# indsensor.net
KiCad netlist of a schematic drawn in EAGLE
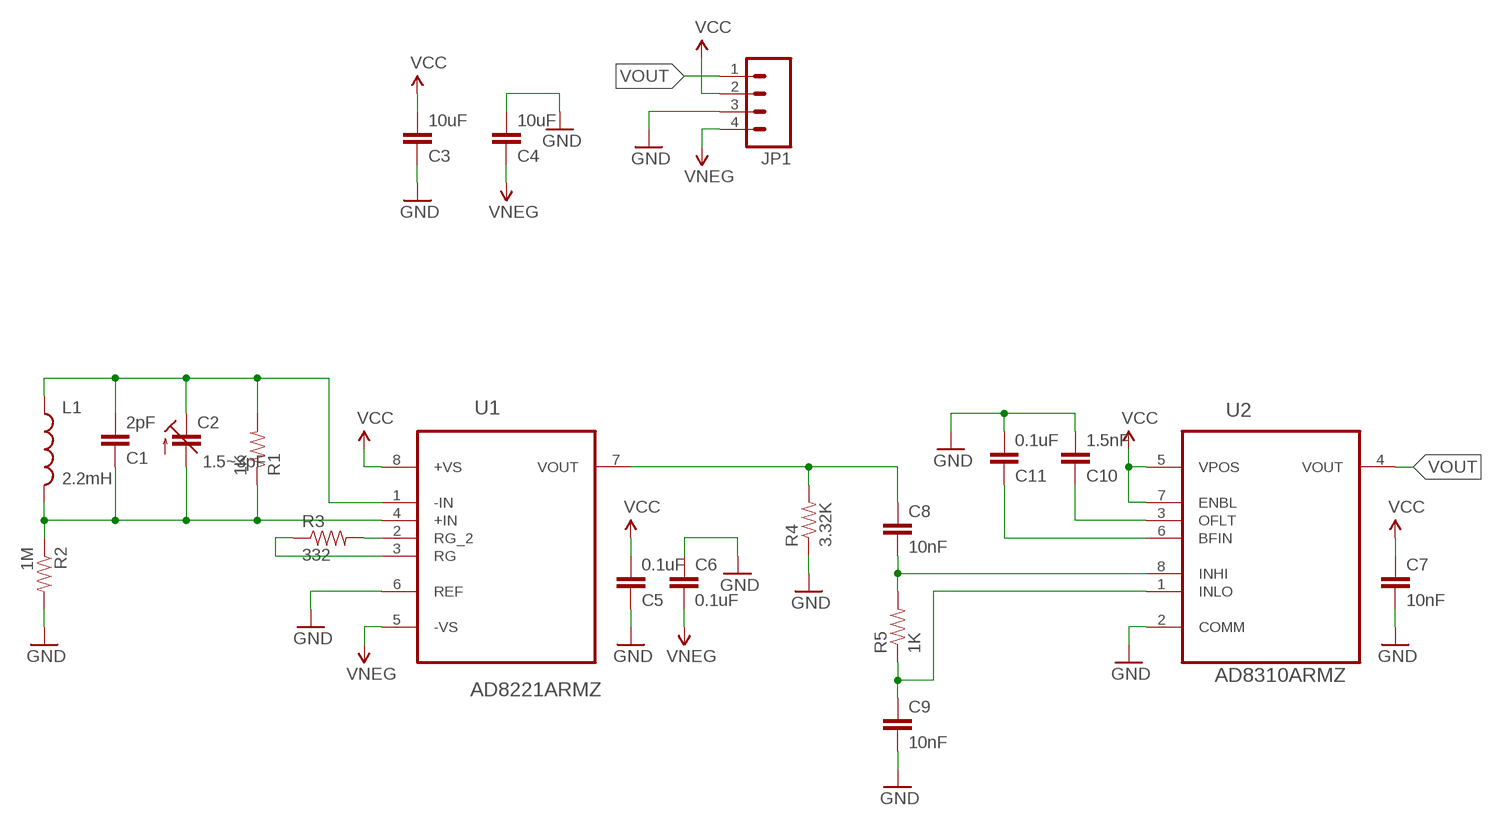
[diagram p0: schematic, sheet 1]

(export (version "E")
  (design (tool "Eeschema 10.0.6"))
  (components
    (comp (ref "C1")
      (value "2pF")
      (footprint "eagle-import:0603-CAP")
      (libsource (lib "eagle-import") (part "CAP0603-CAP"))
    )
    (comp (ref "C2")
      (value "1.5~3pF")
      (footprint "eagle-import:TRIMCAP-TZY")
      (libsource (lib "eagle-import") (part "TRIMCAP-TZY"))
    )
    (comp (ref "C3")
      (value "10uF")
      (footprint "eagle-import:0603-CAP")
      (libsource (lib "eagle-import") (part "CAP0603-CAP"))
    )
    (comp (ref "C4")
      (value "10uF")
      (footprint "eagle-import:0603-CAP")
      (libsource (lib "eagle-import") (part "CAP0603-CAP"))
    )
    (comp (ref "C5")
      (value "0.1uF")
      (footprint "eagle-import:0603-CAP")
      (libsource (lib "eagle-import") (part "CAP0603-CAP"))
    )
    (comp (ref "C6")
      (value "0.1uF")
      (footprint "eagle-import:0603-CAP")
      (libsource (lib "eagle-import") (part "CAP0603-CAP"))
    )
    (comp (ref "C7")
      (value "10nF")
      (footprint "eagle-import:0603-CAP")
      (libsource (lib "eagle-import") (part "CAP0603-CAP"))
    )
    (comp (ref "C8")
      (value "10nF")
      (footprint "eagle-import:0603-CAP")
      (libsource (lib "eagle-import") (part "CAP0603-CAP"))
    )
    (comp (ref "C9")
      (value "10nF")
      (footprint "eagle-import:0603-CAP")
      (libsource (lib "eagle-import") (part "CAP0603-CAP"))
    )
    (comp (ref "C10")
      (value "1.5nF")
      (footprint "eagle-import:0603-CAP")
      (libsource (lib "eagle-import") (part "CAP0603-CAP"))
    )
    (comp (ref "C11")
      (value "0.1uF")
      (footprint "eagle-import:0603-CAP")
      (libsource (lib "eagle-import") (part "CAP0603-CAP"))
    )
    (comp (ref "JP1")
      (value "M04LOCK")
      (footprint "eagle-import:1X04_LOCK")
      (libsource (lib "eagle-import") (part "M04LOCK"))
    )
    (comp (ref "L1")
      (value "2.2mH")
      (footprint "eagle-import:1812")
      (libsource (lib "eagle-import") (part "LQH43N"))
    )
    (comp (ref "R1")
      (value "1K")
      (footprint "eagle-import:0603-RES")
      (libsource (lib "eagle-import") (part "RESISTOR0603"))
    )
    (comp (ref "R2")
      (value "1M")
      (footprint "eagle-import:0603-RES")
      (libsource (lib "eagle-import") (part "RESISTOR0603"))
    )
    (comp (ref "R3")
      (value "332")
      (footprint "eagle-import:0603-RES")
      (libsource (lib "eagle-import") (part "RESISTOR0603"))
    )
    (comp (ref "R4")
      (value "3.32K")
      (footprint "eagle-import:0603-RES")
      (libsource (lib "eagle-import") (part "RESISTOR0603"))
    )
    (comp (ref "R5")
      (value "1K")
      (footprint "eagle-import:0603-RES")
      (libsource (lib "eagle-import") (part "RESISTOR0603"))
    )
    (comp (ref "U1")
      (value "AD8221ARMZ")
      (footprint "eagle-import:SOP65P490X110-8N")
      (libsource (lib "eagle-import") (part "AD8221ARMZ"))
    )
    (comp (ref "U2")
      (value "AD8310ARMZ")
      (footprint "eagle-import:SOP65P490X110-8N")
      (libsource (lib "eagle-import") (part "AD8310ARMZ"))
    )
  )
  (nets
    (net (code "1") (name "GND") (class "Default")
      (node (ref "C10") (pin "2") (pinfunction "2_2") (pintype "passive"))
      (node (ref "C11") (pin "2") (pinfunction "2_2") (pintype "passive"))
      (node (ref "C3") (pin "1") (pinfunction "1_1") (pintype "passive"))
      (node (ref "C4") (pin "2") (pinfunction "2_2") (pintype "passive"))
      (node (ref "C5") (pin "1") (pinfunction "1_1") (pintype "passive"))
      (node (ref "C6") (pin "1") (pinfunction "1_1") (pintype "passive"))
      (node (ref "C7") (pin "2") (pinfunction "2_2") (pintype "passive"))
      (node (ref "C9") (pin "2") (pinfunction "2_2") (pintype "passive"))
      (node (ref "JP1") (pin "3") (pinfunction "3_3") (pintype "passive"))
      (node (ref "R2") (pin "2") (pinfunction "2_2") (pintype "passive"))
      (node (ref "R4") (pin "1") (pinfunction "1_1") (pintype "passive"))
      (node (ref "U1") (pin "6") (pinfunction "REF_6") (pintype "passive"))
      (node (ref "U2") (pin "2") (pinfunction "COMM_2") (pintype "passive"))
    )
    (net (code "2") (name "Net-(C2-A)") (class "Default")
      (node (ref "C1") (pin "1") (pinfunction "1_1") (pintype "passive"))
      (node (ref "C2") (pin "1") (pinfunction "A_1") (pintype "passive"))
      (node (ref "L1") (pin "2") (pinfunction "2_2") (pintype "passive"))
      (node (ref "R1") (pin "1") (pinfunction "1_1") (pintype "passive"))
      (node (ref "R2") (pin "1") (pinfunction "1_1") (pintype "passive"))
      (node (ref "U1") (pin "4") (pinfunction "+IN_4") (pintype "input"))
    )
    (net (code "3") (name "Net-(C2-E)") (class "Default")
      (node (ref "C1") (pin "2") (pinfunction "2_2") (pintype "passive"))
      (node (ref "C2") (pin "2") (pinfunction "E_2") (pintype "passive"))
      (node (ref "L1") (pin "1") (pinfunction "1_1") (pintype "passive"))
      (node (ref "R1") (pin "2") (pinfunction "2_2") (pintype "passive"))
      (node (ref "U1") (pin "1") (pinfunction "-IN_1") (pintype "input"))
    )
    (net (code "4") (name "Net-(U1-RG)") (class "Default")
      (node (ref "R3") (pin "1") (pinfunction "1_1") (pintype "passive"))
      (node (ref "U1") (pin "3") (pinfunction "RG_3") (pintype "input"))
    )
    (net (code "5") (name "Net-(U1-RG_2)") (class "Default")
      (node (ref "R3") (pin "2") (pinfunction "2_2") (pintype "passive"))
      (node (ref "U1") (pin "2") (pinfunction "RG_2_2") (pintype "input"))
    )
    (net (code "6") (name "Net-(U1-VOUT)") (class "Default")
      (node (ref "C8") (pin "1") (pinfunction "1_1") (pintype "passive"))
      (node (ref "R4") (pin "2") (pinfunction "2_2") (pintype "passive"))
      (node (ref "U1") (pin "7") (pinfunction "VOUT_7") (pintype "output"))
    )
    (net (code "7") (name "Net-(U2-BFIN)") (class "Default")
      (node (ref "C11") (pin "1") (pinfunction "1_1") (pintype "passive"))
      (node (ref "U2") (pin "6") (pinfunction "BFIN_6") (pintype "input"))
    )
    (net (code "8") (name "Net-(U2-INHI)") (class "Default")
      (node (ref "C8") (pin "2") (pinfunction "2_2") (pintype "passive"))
      (node (ref "R5") (pin "2") (pinfunction "2_2") (pintype "passive"))
      (node (ref "U2") (pin "8") (pinfunction "INHI_8") (pintype "input"))
    )
    (net (code "9") (name "Net-(U2-INLO)") (class "Default")
      (node (ref "C9") (pin "1") (pinfunction "1_1") (pintype "passive"))
      (node (ref "R5") (pin "1") (pinfunction "1_1") (pintype "passive"))
      (node (ref "U2") (pin "1") (pinfunction "INLO_1") (pintype "input"))
    )
    (net (code "10") (name "Net-(U2-OFLT)") (class "Default")
      (node (ref "C10") (pin "1") (pinfunction "1_1") (pintype "passive"))
      (node (ref "U2") (pin "3") (pinfunction "OFLT_3") (pintype "passive"))
    )
    (net (code "11") (name "VCC") (class "Default")
      (node (ref "C3") (pin "2") (pinfunction "2_2") (pintype "passive"))
      (node (ref "C5") (pin "2") (pinfunction "2_2") (pintype "passive"))
      (node (ref "C7") (pin "1") (pinfunction "1_1") (pintype "passive"))
      (node (ref "JP1") (pin "2") (pinfunction "2_2") (pintype "passive"))
      (node (ref "U1") (pin "8") (pinfunction "+VS_8") (pintype "power_in"))
      (node (ref "U2") (pin "5") (pinfunction "VPOS_5") (pintype "power_in"))
      (node (ref "U2") (pin "7") (pinfunction "ENBL_7") (pintype "input"))
    )
    (net (code "12") (name "VNEG") (class "Default")
      (node (ref "C4") (pin "1") (pinfunction "1_1") (pintype "passive"))
      (node (ref "C6") (pin "2") (pinfunction "2_2") (pintype "passive"))
      (node (ref "JP1") (pin "4") (pinfunction "4_4") (pintype "passive"))
      (node (ref "U1") (pin "5") (pinfunction "-VS_5") (pintype "power_in"))
    )
    (net (code "13") (name "VOUT") (class "Default")
      (node (ref "JP1") (pin "1") (pinfunction "1_1") (pintype "passive"))
      (node (ref "U2") (pin "4") (pinfunction "VOUT_4") (pintype "output"))
    )
  )
)
